# cvPal_sound_study.net
KiCad netlist of a schematic drawn in EAGLE
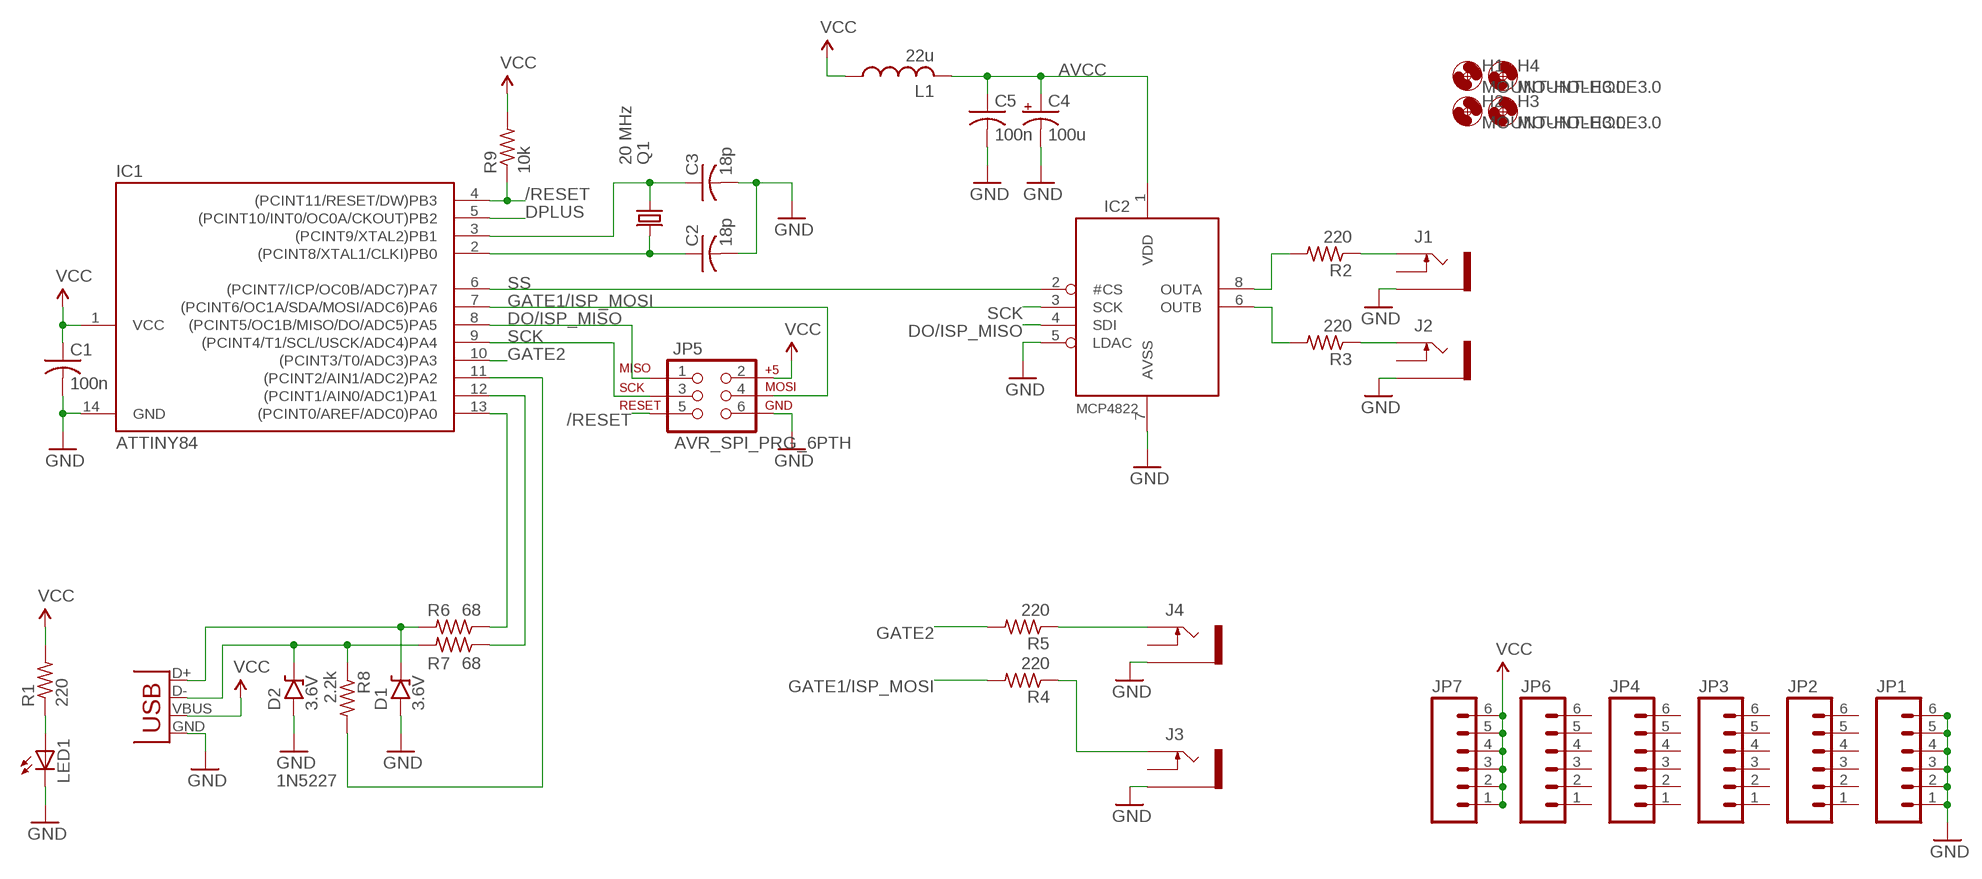
[diagram p0: schematic, sheet 1]

(export (version "E")
  (design (tool "Eeschema 10.0.6"))
  (components
    (comp (ref "C1")
      (value "100n")
      (footprint "eagle-import:C025-025X050")
      (libsource (lib "eagle-import") (part "C-US025-025X050"))
    )
    (comp (ref "C2")
      (value "18p")
      (footprint "eagle-import:C025-025X050")
      (libsource (lib "eagle-import") (part "C-US025-025X050"))
    )
    (comp (ref "C3")
      (value "18p")
      (footprint "eagle-import:C025-025X050")
      (libsource (lib "eagle-import") (part "C-US025-025X050"))
    )
    (comp (ref "C4")
      (value "100u")
      (footprint "eagle-import:E2,5-7")
      (libsource (lib "eagle-import") (part "CPOL-USE2.5-7"))
    )
    (comp (ref "C5")
      (value "100n")
      (footprint "eagle-import:C025-025X050")
      (libsource (lib "eagle-import") (part "C-US025-025X050"))
    )
    (comp (ref "D1")
      (value "3.6V")
      (footprint "eagle-import:D-5")
      (libsource (lib "eagle-import") (part "1N47XXDO35"))
    )
    (comp (ref "D2")
      (value "3.6V")
      (footprint "eagle-import:D-5")
      (libsource (lib "eagle-import") (part "1N47XXDO35"))
    )
    (comp (ref "H1")
      (value "MOUNT-HOLE3.0")
      (footprint "eagle-import:3,0")
      (libsource (lib "eagle-import") (part "MOUNT-HOLE3.0"))
    )
    (comp (ref "H2")
      (value "MOUNT-HOLE3.0")
      (footprint "eagle-import:3,0")
      (libsource (lib "eagle-import") (part "MOUNT-HOLE3.0"))
    )
    (comp (ref "H3")
      (value "MOUNT-HOLE3.0")
      (footprint "eagle-import:3,0")
      (libsource (lib "eagle-import") (part "MOUNT-HOLE3.0"))
    )
    (comp (ref "H4")
      (value "MOUNT-HOLE3.0")
      (footprint "eagle-import:3,0")
      (libsource (lib "eagle-import") (part "MOUNT-HOLE3.0"))
    )
    (comp (ref "IC1")
      (value "ATTINY84")
      (footprint "eagle-import:DIL14")
      (libsource (lib "eagle-import") (part "ATTINY24/44/84-PU"))
    )
    (comp (ref "IC2")
      (value "MCP4822")
      (footprint "eagle-import:DIL08")
      (libsource (lib "eagle-import") (part "MCP4822"))
    )
    (comp (ref "J1")
      (value "1503_12")
      (footprint "eagle-import:1503_12")
      (libsource (lib "eagle-import") (part "1503_12"))
    )
    (comp (ref "J2")
      (value "1503_12")
      (footprint "eagle-import:1503_12")
      (libsource (lib "eagle-import") (part "1503_12"))
    )
    (comp (ref "J3")
      (value "1503_12")
      (footprint "eagle-import:1503_12")
      (libsource (lib "eagle-import") (part "1503_12"))
    )
    (comp (ref "J4")
      (value "1503_12")
      (footprint "eagle-import:1503_12")
      (libsource (lib "eagle-import") (part "1503_12"))
    )
    (comp (ref "JP1")
      (value "M06SIP")
      (footprint "eagle-import:1X06")
      (libsource (lib "eagle-import") (part "M06SIP"))
    )
    (comp (ref "JP2")
      (value "M06SIP")
      (footprint "eagle-import:1X06")
      (libsource (lib "eagle-import") (part "M06SIP"))
    )
    (comp (ref "JP3")
      (value "M06SIP")
      (footprint "eagle-import:1X06")
      (libsource (lib "eagle-import") (part "M06SIP"))
    )
    (comp (ref "JP4")
      (value "M06SIP")
      (footprint "eagle-import:1X06")
      (libsource (lib "eagle-import") (part "M06SIP"))
    )
    (comp (ref "JP5")
      (value "AVR_SPI_PRG_6PTH")
      (footprint "eagle-import:2X3")
      (libsource (lib "eagle-import") (part "AVR_SPI_PRG_6PTH"))
    )
    (comp (ref "JP6")
      (value "M06SIP")
      (footprint "eagle-import:1X06")
      (libsource (lib "eagle-import") (part "M06SIP"))
    )
    (comp (ref "JP7")
      (value "M06SIP")
      (footprint "eagle-import:1X06")
      (libsource (lib "eagle-import") (part "M06SIP"))
    )
    (comp (ref "L1")
      (value "22u")
      (footprint "eagle-import:0207_10")
      (libsource (lib "eagle-import") (part "L-US0207/10"))
    )
    (comp (ref "LED1")
      (value "LED5MM")
      (footprint "eagle-import:LED5MM")
      (libsource (lib "eagle-import") (part "LED5MM"))
    )
    (comp (ref "Q1")
      (value "20 MHz")
      (footprint "eagle-import:HC49_S")
      (libsource (lib "eagle-import") (part "CRYSTALHC49S"))
    )
    (comp (ref "R1")
      (value "220")
      (footprint "eagle-import:0204_7")
      (libsource (lib "eagle-import") (part "R-US_0204/7"))
    )
    (comp (ref "R2")
      (value "220")
      (footprint "eagle-import:0204_7")
      (libsource (lib "eagle-import") (part "R-US_0204/7"))
    )
    (comp (ref "R3")
      (value "220")
      (footprint "eagle-import:0204_7")
      (libsource (lib "eagle-import") (part "R-US_0204/7"))
    )
    (comp (ref "R4")
      (value "220")
      (footprint "eagle-import:0204_7")
      (libsource (lib "eagle-import") (part "R-US_0204/7"))
    )
    (comp (ref "R5")
      (value "220")
      (footprint "eagle-import:0204_7")
      (libsource (lib "eagle-import") (part "R-US_0204/7"))
    )
    (comp (ref "R6")
      (value "68")
      (footprint "eagle-import:0204_7")
      (libsource (lib "eagle-import") (part "R-US_0204/7"))
    )
    (comp (ref "R7")
      (value "68")
      (footprint "eagle-import:0204_7")
      (libsource (lib "eagle-import") (part "R-US_0204/7"))
    )
    (comp (ref "R8")
      (value "2.2k")
      (footprint "eagle-import:0204_7")
      (libsource (lib "eagle-import") (part "R-US_0204/7"))
    )
    (comp (ref "R9")
      (value "10k")
      (footprint "eagle-import:0204_7")
      (libsource (lib "eagle-import") (part "R-US_0204/7"))
    )
    (comp (ref "X2")
      (value "USBPTH")
      (footprint "eagle-import:USB-B-PTH")
      (libsource (lib "eagle-import") (part "USBPTH"))
    )
  )
  (nets
    (net (code "1") (name "/AVCC") (class "Default")
      (node (ref "C4") (pin "+") (pinfunction "+_+") (pintype "passive"))
      (node (ref "C5") (pin "1") (pinfunction "1_1") (pintype "passive"))
      (node (ref "IC2") (pin "1") (pinfunction "VDD_1") (pintype "power_in"))
      (node (ref "L1") (pin "2") (pinfunction "2_2") (pintype "passive"))
    )
    (net (code "2") (name "/DO{slash}ISP_MISO") (class "Default")
      (node (ref "IC1") (pin "8") (pinfunction "(PCINT5/OC1B/MISO/DO/ADC5)PA5_8") (pintype "bidirectional"))
      (node (ref "IC2") (pin "4") (pinfunction "SDI_4") (pintype "input"))
      (node (ref "JP5") (pin "1") (pinfunction "1_1") (pintype "passive"))
    )
    (net (code "3") (name "/DPLUS") (class "Default")
      (node (ref "IC1") (pin "13") (pinfunction "(PCINT0/AREF/ADC0)PA0_13") (pintype "bidirectional"))
      (node (ref "IC1") (pin "5") (pinfunction "(PCINT10/INT0/OC0A/CKOUT)PB2_5") (pintype "bidirectional"))
      (node (ref "R6") (pin "1") (pinfunction "1_1") (pintype "passive"))
    )
    (net (code "4") (name "/GATE1{slash}ISP_MOSI") (class "Default")
      (node (ref "IC1") (pin "7") (pinfunction "(PCINT6/OC1A/SDA/MOSI/ADC6)PA6_7") (pintype "bidirectional"))
      (node (ref "JP5") (pin "4") (pinfunction "4_4") (pintype "passive"))
      (node (ref "R4") (pin "2") (pinfunction "2_2") (pintype "passive"))
    )
    (net (code "5") (name "/GATE2") (class "Default")
      (node (ref "IC1") (pin "10") (pinfunction "(PCINT3/T0/ADC3)PA3_10") (pintype "bidirectional"))
      (node (ref "R5") (pin "2") (pinfunction "2_2") (pintype "passive"))
    )
    (net (code "6") (name "/SCK") (class "Default")
      (node (ref "IC1") (pin "9") (pinfunction "(PCINT4/T1/SCL/USCK/ADC4)PA4_9") (pintype "bidirectional"))
      (node (ref "IC2") (pin "3") (pinfunction "SCK_3") (pintype "input"))
      (node (ref "JP5") (pin "3") (pinfunction "3_3") (pintype "passive"))
    )
    (net (code "7") (name "/SS") (class "Default")
      (node (ref "IC1") (pin "6") (pinfunction "(PCINT7/ICP/OC0B/ADC7)PA7_6") (pintype "bidirectional"))
      (node (ref "IC2") (pin "2") (pinfunction "#CS_2") (pintype "input"))
    )
    (net (code "8") (name "/{slash}RESET") (class "Default")
      (node (ref "IC1") (pin "4") (pinfunction "(PCINT11/RESET/DW)PB3_4") (pintype "bidirectional"))
      (node (ref "JP5") (pin "5") (pinfunction "5_5") (pintype "passive"))
      (node (ref "R9") (pin "1") (pinfunction "1_1") (pintype "passive"))
    )
    (net (code "9") (name "GND") (class "Default")
      (node (ref "C1") (pin "2") (pinfunction "2_2") (pintype "passive"))
      (node (ref "C2") (pin "2") (pinfunction "2_2") (pintype "passive"))
      (node (ref "C3") (pin "2") (pinfunction "2_2") (pintype "passive"))
      (node (ref "C4") (pin "-") (pinfunction "-_-") (pintype "passive"))
      (node (ref "C5") (pin "2") (pinfunction "2_2") (pintype "passive"))
      (node (ref "D1") (pin "A") (pinfunction "A_A") (pintype "passive"))
      (node (ref "D2") (pin "A") (pinfunction "A_A") (pintype "passive"))
      (node (ref "IC1") (pin "14") (pinfunction "GND_14") (pintype "power_in"))
      (node (ref "IC2") (pin "5") (pinfunction "LDAC_5") (pintype "input"))
      (node (ref "IC2") (pin "7") (pinfunction "AVSS_7") (pintype "power_in"))
      (node (ref "J1") (pin "5") (pinfunction "1_5") (pintype "passive"))
      (node (ref "J2") (pin "5") (pinfunction "1_5") (pintype "passive"))
      (node (ref "J3") (pin "5") (pinfunction "1_5") (pintype "passive"))
      (node (ref "J4") (pin "5") (pinfunction "1_5") (pintype "passive"))
      (node (ref "JP1") (pin "1") (pinfunction "1_1") (pintype "passive"))
      (node (ref "JP1") (pin "2") (pinfunction "2_2") (pintype "passive"))
      (node (ref "JP1") (pin "3") (pinfunction "3_3") (pintype "passive"))
      (node (ref "JP1") (pin "4") (pinfunction "4_4") (pintype "passive"))
      (node (ref "JP1") (pin "5") (pinfunction "5_5") (pintype "passive"))
      (node (ref "JP1") (pin "6") (pinfunction "6_6") (pintype "passive"))
      (node (ref "JP5") (pin "6") (pinfunction "6_6") (pintype "passive"))
      (node (ref "LED1") (pin "K") (pinfunction "C_K") (pintype "passive"))
      (node (ref "X2") (pin "GND") (pinfunction "GND_GND") (pintype "bidirectional"))
    )
    (net (code "10") (name "Net-(D1-PadC)") (class "Default")
      (node (ref "D1") (pin "C") (pinfunction "C_C") (pintype "passive"))
      (node (ref "R6") (pin "2") (pinfunction "2_2") (pintype "passive"))
      (node (ref "X2") (pin "D+") (pinfunction "D+_D+") (pintype "bidirectional"))
    )
    (net (code "11") (name "Net-(D2-PadC)") (class "Default")
      (node (ref "D2") (pin "C") (pinfunction "C_C") (pintype "passive"))
      (node (ref "R7") (pin "2") (pinfunction "2_2") (pintype "passive"))
      (node (ref "R8") (pin "1") (pinfunction "1_1") (pintype "passive"))
      (node (ref "X2") (pin "D-") (pinfunction "D-_D-") (pintype "bidirectional"))
    )
    (net (code "12") (name "Net-(IC1-(PCINT1{slash}AIN0{slash}ADC1)PA1)") (class "Default")
      (node (ref "IC1") (pin "12") (pinfunction "(PCINT1/AIN0/ADC1)PA1_12") (pintype "bidirectional"))
      (node (ref "R7") (pin "1") (pinfunction "1_1") (pintype "passive"))
    )
    (net (code "13") (name "Net-(IC1-(PCINT2{slash}AIN1{slash}ADC2)PA2)") (class "Default")
      (node (ref "IC1") (pin "11") (pinfunction "(PCINT2/AIN1/ADC2)PA2_11") (pintype "bidirectional"))
      (node (ref "R8") (pin "2") (pinfunction "2_2") (pintype "passive"))
    )
    (net (code "14") (name "Net-(IC1-(PCINT8{slash}XTAL1{slash}CLKI)PB0)") (class "Default")
      (node (ref "C2") (pin "1") (pinfunction "1_1") (pintype "passive"))
      (node (ref "IC1") (pin "2") (pinfunction "(PCINT8/XTAL1/CLKI)PB0_2") (pintype "bidirectional"))
      (node (ref "Q1") (pin "2") (pinfunction "2_2") (pintype "passive"))
    )
    (net (code "15") (name "Net-(IC1-(PCINT9{slash}XTAL2)PB1)") (class "Default")
      (node (ref "C3") (pin "1") (pinfunction "1_1") (pintype "passive"))
      (node (ref "IC1") (pin "3") (pinfunction "(PCINT9/XTAL2)PB1_3") (pintype "bidirectional"))
      (node (ref "Q1") (pin "1") (pinfunction "1_1") (pintype "passive"))
    )
    (net (code "16") (name "Net-(IC2-OUTA)") (class "Default")
      (node (ref "IC2") (pin "8") (pinfunction "OUTA_8") (pintype "output"))
      (node (ref "R2") (pin "2") (pinfunction "2_2") (pintype "passive"))
    )
    (net (code "17") (name "Net-(IC2-OUTB)") (class "Default")
      (node (ref "IC2") (pin "6") (pinfunction "OUTB_6") (pintype "output"))
      (node (ref "R3") (pin "2") (pinfunction "2_2") (pintype "passive"))
    )
    (net (code "18") (name "Net-(J1-2)") (class "Default")
      (node (ref "J1") (pin "3") (pinfunction "2_3") (pintype "passive"))
      (node (ref "R2") (pin "1") (pinfunction "1_1") (pintype "passive"))
    )
    (net (code "19") (name "Net-(J2-2)") (class "Default")
      (node (ref "J2") (pin "3") (pinfunction "2_3") (pintype "passive"))
      (node (ref "R3") (pin "1") (pinfunction "1_1") (pintype "passive"))
    )
    (net (code "20") (name "Net-(J3-2)") (class "Default")
      (node (ref "J3") (pin "3") (pinfunction "2_3") (pintype "passive"))
      (node (ref "R4") (pin "1") (pinfunction "1_1") (pintype "passive"))
    )
    (net (code "21") (name "Net-(J4-2)") (class "Default")
      (node (ref "J4") (pin "3") (pinfunction "2_3") (pintype "passive"))
      (node (ref "R5") (pin "1") (pinfunction "1_1") (pintype "passive"))
    )
    (net (code "22") (name "Net-(LED1-PadA)") (class "Default")
      (node (ref "LED1") (pin "A") (pinfunction "A_A") (pintype "passive"))
      (node (ref "R1") (pin "1") (pinfunction "1_1") (pintype "passive"))
    )
    (net (code "23") (name "VCC") (class "Default")
      (node (ref "C1") (pin "1") (pinfunction "1_1") (pintype "passive"))
      (node (ref "IC1") (pin "1") (pinfunction "VCC_1") (pintype "power_in"))
      (node (ref "JP5") (pin "2") (pinfunction "2_2") (pintype "passive"))
      (node (ref "JP7") (pin "1") (pinfunction "1_1") (pintype "passive"))
      (node (ref "JP7") (pin "2") (pinfunction "2_2") (pintype "passive"))
      (node (ref "JP7") (pin "3") (pinfunction "3_3") (pintype "passive"))
      (node (ref "JP7") (pin "4") (pinfunction "4_4") (pintype "passive"))
      (node (ref "JP7") (pin "5") (pinfunction "5_5") (pintype "passive"))
      (node (ref "JP7") (pin "6") (pinfunction "6_6") (pintype "passive"))
      (node (ref "L1") (pin "1") (pinfunction "1_1") (pintype "passive"))
      (node (ref "R1") (pin "2") (pinfunction "2_2") (pintype "passive"))
      (node (ref "R9") (pin "2") (pinfunction "2_2") (pintype "passive"))
      (node (ref "X2") (pin "VBUS") (pinfunction "VBUS_VBUS") (pintype "bidirectional"))
    )
    (net (code "24") (name "unconnected-(J1-3-Pad4)") (class "Default")
      (node (ref "J1") (pin "4") (pinfunction "3_4") (pintype "passive"))
    )
    (net (code "25") (name "unconnected-(J2-3-Pad4)") (class "Default")
      (node (ref "J2") (pin "4") (pinfunction "3_4") (pintype "passive"))
    )
    (net (code "26") (name "unconnected-(J3-3-Pad4)") (class "Default")
      (node (ref "J3") (pin "4") (pinfunction "3_4") (pintype "passive"))
    )
    (net (code "27") (name "unconnected-(J4-3-Pad4)") (class "Default")
      (node (ref "J4") (pin "4") (pinfunction "3_4") (pintype "passive"))
    )
    (net (code "28") (name "unconnected-(JP2-Pad1)") (class "Default")
      (node (ref "JP2") (pin "1") (pinfunction "1_1") (pintype "passive"))
    )
    (net (code "29") (name "unconnected-(JP2-Pad2)") (class "Default")
      (node (ref "JP2") (pin "2") (pinfunction "2_2") (pintype "passive"))
    )
    (net (code "30") (name "unconnected-(JP2-Pad3)") (class "Default")
      (node (ref "JP2") (pin "3") (pinfunction "3_3") (pintype "passive"))
    )
    (net (code "31") (name "unconnected-(JP2-Pad4)") (class "Default")
      (node (ref "JP2") (pin "4") (pinfunction "4_4") (pintype "passive"))
    )
    (net (code "32") (name "unconnected-(JP2-Pad5)") (class "Default")
      (node (ref "JP2") (pin "5") (pinfunction "5_5") (pintype "passive"))
    )
    (net (code "33") (name "unconnected-(JP2-Pad6)") (class "Default")
      (node (ref "JP2") (pin "6") (pinfunction "6_6") (pintype "passive"))
    )
    (net (code "34") (name "unconnected-(JP3-Pad1)") (class "Default")
      (node (ref "JP3") (pin "1") (pinfunction "1_1") (pintype "passive"))
    )
    (net (code "35") (name "unconnected-(JP3-Pad2)") (class "Default")
      (node (ref "JP3") (pin "2") (pinfunction "2_2") (pintype "passive"))
    )
    (net (code "36") (name "unconnected-(JP3-Pad3)") (class "Default")
      (node (ref "JP3") (pin "3") (pinfunction "3_3") (pintype "passive"))
    )
    (net (code "37") (name "unconnected-(JP3-Pad4)") (class "Default")
      (node (ref "JP3") (pin "4") (pinfunction "4_4") (pintype "passive"))
    )
    (net (code "38") (name "unconnected-(JP3-Pad5)") (class "Default")
      (node (ref "JP3") (pin "5") (pinfunction "5_5") (pintype "passive"))
    )
    (net (code "39") (name "unconnected-(JP3-Pad6)") (class "Default")
      (node (ref "JP3") (pin "6") (pinfunction "6_6") (pintype "passive"))
    )
    (net (code "40") (name "unconnected-(JP4-Pad1)") (class "Default")
      (node (ref "JP4") (pin "1") (pinfunction "1_1") (pintype "passive"))
    )
    (net (code "41") (name "unconnected-(JP4-Pad2)") (class "Default")
      (node (ref "JP4") (pin "2") (pinfunction "2_2") (pintype "passive"))
    )
    (net (code "42") (name "unconnected-(JP4-Pad3)") (class "Default")
      (node (ref "JP4") (pin "3") (pinfunction "3_3") (pintype "passive"))
    )
    (net (code "43") (name "unconnected-(JP4-Pad4)") (class "Default")
      (node (ref "JP4") (pin "4") (pinfunction "4_4") (pintype "passive"))
    )
    (net (code "44") (name "unconnected-(JP4-Pad5)") (class "Default")
      (node (ref "JP4") (pin "5") (pinfunction "5_5") (pintype "passive"))
    )
    (net (code "45") (name "unconnected-(JP4-Pad6)") (class "Default")
      (node (ref "JP4") (pin "6") (pinfunction "6_6") (pintype "passive"))
    )
    (net (code "46") (name "unconnected-(JP6-Pad1)") (class "Default")
      (node (ref "JP6") (pin "1") (pinfunction "1_1") (pintype "passive"))
    )
    (net (code "47") (name "unconnected-(JP6-Pad2)") (class "Default")
      (node (ref "JP6") (pin "2") (pinfunction "2_2") (pintype "passive"))
    )
    (net (code "48") (name "unconnected-(JP6-Pad3)") (class "Default")
      (node (ref "JP6") (pin "3") (pinfunction "3_3") (pintype "passive"))
    )
    (net (code "49") (name "unconnected-(JP6-Pad4)") (class "Default")
      (node (ref "JP6") (pin "4") (pinfunction "4_4") (pintype "passive"))
    )
    (net (code "50") (name "unconnected-(JP6-Pad5)") (class "Default")
      (node (ref "JP6") (pin "5") (pinfunction "5_5") (pintype "passive"))
    )
    (net (code "51") (name "unconnected-(JP6-Pad6)") (class "Default")
      (node (ref "JP6") (pin "6") (pinfunction "6_6") (pintype "passive"))
    )
  )
)
